# Test_Points.net
KiCad netlist of a schematic drawn in Altium Designer
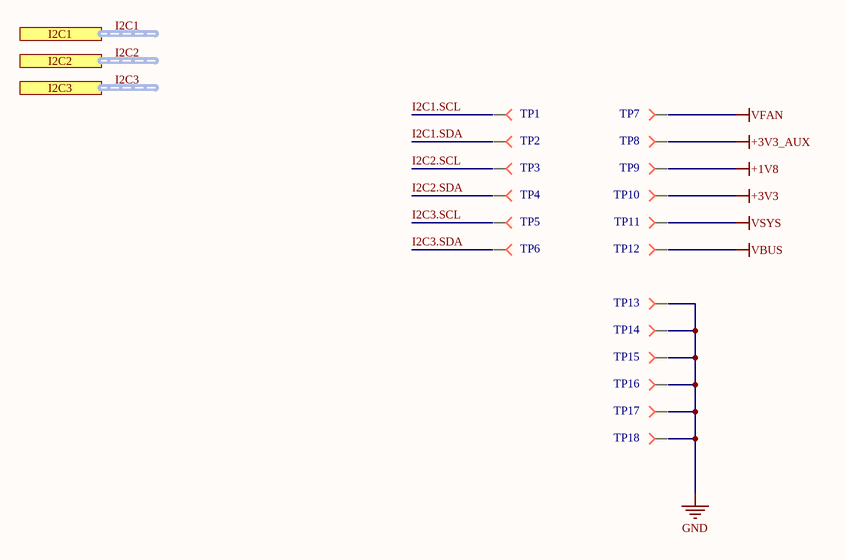
[diagram p0: Test_Points.SchDoc]

(export (version "E")
  (design (tool "Eeschema 10.0.6"))
  (components
    (comp (ref "TP1")
      (value "Test Point Pad")
      (footprint "Testpoint")
      (description "Test Point. There is nothing to buy or mount.")
      (libsource (lib "") (part "Test Point Pad_1"))
    )
    (comp (ref "TP2")
      (value "Test Point Pad")
      (footprint "Testpoint")
      (description "Test Point. There is nothing to buy or mount.")
      (libsource (lib "") (part "Test Point Pad_1"))
    )
    (comp (ref "TP3")
      (value "Test Point Pad")
      (footprint "Testpoint")
      (description "Test Point. There is nothing to buy or mount.")
      (libsource (lib "") (part "Test Point Pad_1"))
    )
    (comp (ref "TP4")
      (value "Test Point Pad")
      (footprint "Testpoint")
      (description "Test Point. There is nothing to buy or mount.")
      (libsource (lib "") (part "Test Point Pad_1"))
    )
    (comp (ref "TP5")
      (value "Test Point Pad")
      (footprint "Testpoint")
      (description "Test Point. There is nothing to buy or mount.")
      (libsource (lib "") (part "Test Point Pad_1"))
    )
    (comp (ref "TP6")
      (value "Test Point Pad")
      (footprint "Testpoint")
      (description "Test Point. There is nothing to buy or mount.")
      (libsource (lib "") (part "Test Point Pad_1"))
    )
    (comp (ref "TP7")
      (value "Test Point Pad")
      (footprint "Testpoint")
      (description "Test Point. There is nothing to buy or mount.")
      (libsource (lib "BLDC_Motor_Driver") (part "Test Point Pad"))
    )
    (comp (ref "TP8")
      (value "Test Point Pad")
      (footprint "Testpoint")
      (description "Test Point. There is nothing to buy or mount.")
      (libsource (lib "BLDC_Motor_Driver") (part "Test Point Pad"))
    )
    (comp (ref "TP9")
      (value "Test Point Pad")
      (footprint "Testpoint")
      (description "Test Point. There is nothing to buy or mount.")
      (libsource (lib "BLDC_Motor_Driver") (part "Test Point Pad"))
    )
    (comp (ref "TP10")
      (value "Test Point Pad")
      (footprint "Testpoint")
      (description "Test Point. There is nothing to buy or mount.")
      (libsource (lib "BLDC_Motor_Driver") (part "Test Point Pad"))
    )
    (comp (ref "TP11")
      (value "Test Point Pad")
      (footprint "Testpoint")
      (description "Test Point. There is nothing to buy or mount.")
      (libsource (lib "BLDC_Motor_Driver") (part "Test Point Pad"))
    )
    (comp (ref "TP12")
      (value "Test Point Pad")
      (footprint "Testpoint")
      (description "Test Point. There is nothing to buy or mount.")
      (libsource (lib "BLDC_Motor_Driver") (part "Test Point Pad"))
    )
    (comp (ref "TP13")
      (value "Test Point Pad")
      (footprint "Testpoint")
      (description "Test Point. There is nothing to buy or mount.")
      (libsource (lib "BLDC_Motor_Driver") (part "Test Point Pad"))
    )
    (comp (ref "TP14")
      (value "Test Point Pad")
      (footprint "Testpoint")
      (description "Test Point. There is nothing to buy or mount.")
      (libsource (lib "BLDC_Motor_Driver") (part "Test Point Pad"))
    )
    (comp (ref "TP15")
      (value "Test Point Pad")
      (footprint "Testpoint")
      (description "Test Point. There is nothing to buy or mount.")
      (libsource (lib "BLDC_Motor_Driver") (part "Test Point Pad"))
    )
    (comp (ref "TP16")
      (value "Test Point Pad")
      (footprint "Testpoint")
      (description "Test Point. There is nothing to buy or mount.")
      (libsource (lib "BLDC_Motor_Driver") (part "Test Point Pad"))
    )
    (comp (ref "TP17")
      (value "Test Point Pad")
      (footprint "Testpoint")
      (description "Test Point. There is nothing to buy or mount.")
      (libsource (lib "BLDC_Motor_Driver") (part "Test Point Pad"))
    )
    (comp (ref "TP18")
      (value "Test Point Pad")
      (footprint "Testpoint")
      (description "Test Point. There is nothing to buy or mount.")
      (libsource (lib "BLDC_Motor_Driver") (part "Test Point Pad"))
    )
  )
  (nets
    (net (code "4") (name "+1V8") (class "Default")
      (node (ref "TP9") (pin "1") (pinfunction "1_1") (pintype "passive"))
    )
    (net (code "5") (name "+3V3") (class "Default")
      (node (ref "TP10") (pin "1") (pinfunction "1_1") (pintype "passive"))
    )
    (net (code "6") (name "+3V3_AUX") (class "Default")
      (node (ref "TP8") (pin "1") (pinfunction "1_1") (pintype "passive"))
    )
    (net (code "7") (name "/I2C1.SCL") (class "Default")
      (node (ref "TP1") (pin "1") (pinfunction "1_1") (pintype "passive"))
    )
    (net (code "8") (name "/I2C1.SDA") (class "Default")
      (node (ref "TP2") (pin "1") (pinfunction "1_1") (pintype "passive"))
    )
    (net (code "9") (name "/I2C2.SCL") (class "Default")
      (node (ref "TP3") (pin "1") (pinfunction "1_1") (pintype "passive"))
    )
    (net (code "10") (name "/I2C2.SDA") (class "Default")
      (node (ref "TP4") (pin "1") (pinfunction "1_1") (pintype "passive"))
    )
    (net (code "11") (name "/I2C3.SCL") (class "Default")
      (node (ref "TP5") (pin "1") (pinfunction "1_1") (pintype "passive"))
    )
    (net (code "12") (name "/I2C3.SDA") (class "Default")
      (node (ref "TP6") (pin "1") (pinfunction "1_1") (pintype "passive"))
    )
    (net (code "16") (name "GND") (class "Default")
      (node (ref "TP13") (pin "1") (pinfunction "1_1") (pintype "passive"))
      (node (ref "TP14") (pin "1") (pinfunction "1_1") (pintype "passive"))
      (node (ref "TP15") (pin "1") (pinfunction "1_1") (pintype "passive"))
      (node (ref "TP16") (pin "1") (pinfunction "1_1") (pintype "passive"))
      (node (ref "TP17") (pin "1") (pinfunction "1_1") (pintype "passive"))
      (node (ref "TP18") (pin "1") (pinfunction "1_1") (pintype "passive"))
    )
    (net (code "17") (name "VBUS") (class "Default")
      (node (ref "TP12") (pin "1") (pinfunction "1_1") (pintype "passive"))
    )
    (net (code "18") (name "VFAN") (class "Default")
      (node (ref "TP7") (pin "1") (pinfunction "1_1") (pintype "passive"))
    )
    (net (code "19") (name "VSYS") (class "Default")
      (node (ref "TP11") (pin "1") (pinfunction "1_1") (pintype "passive"))
    )
  )
)
